# v1.net
KiCad netlist of a schematic drawn in EAGLE
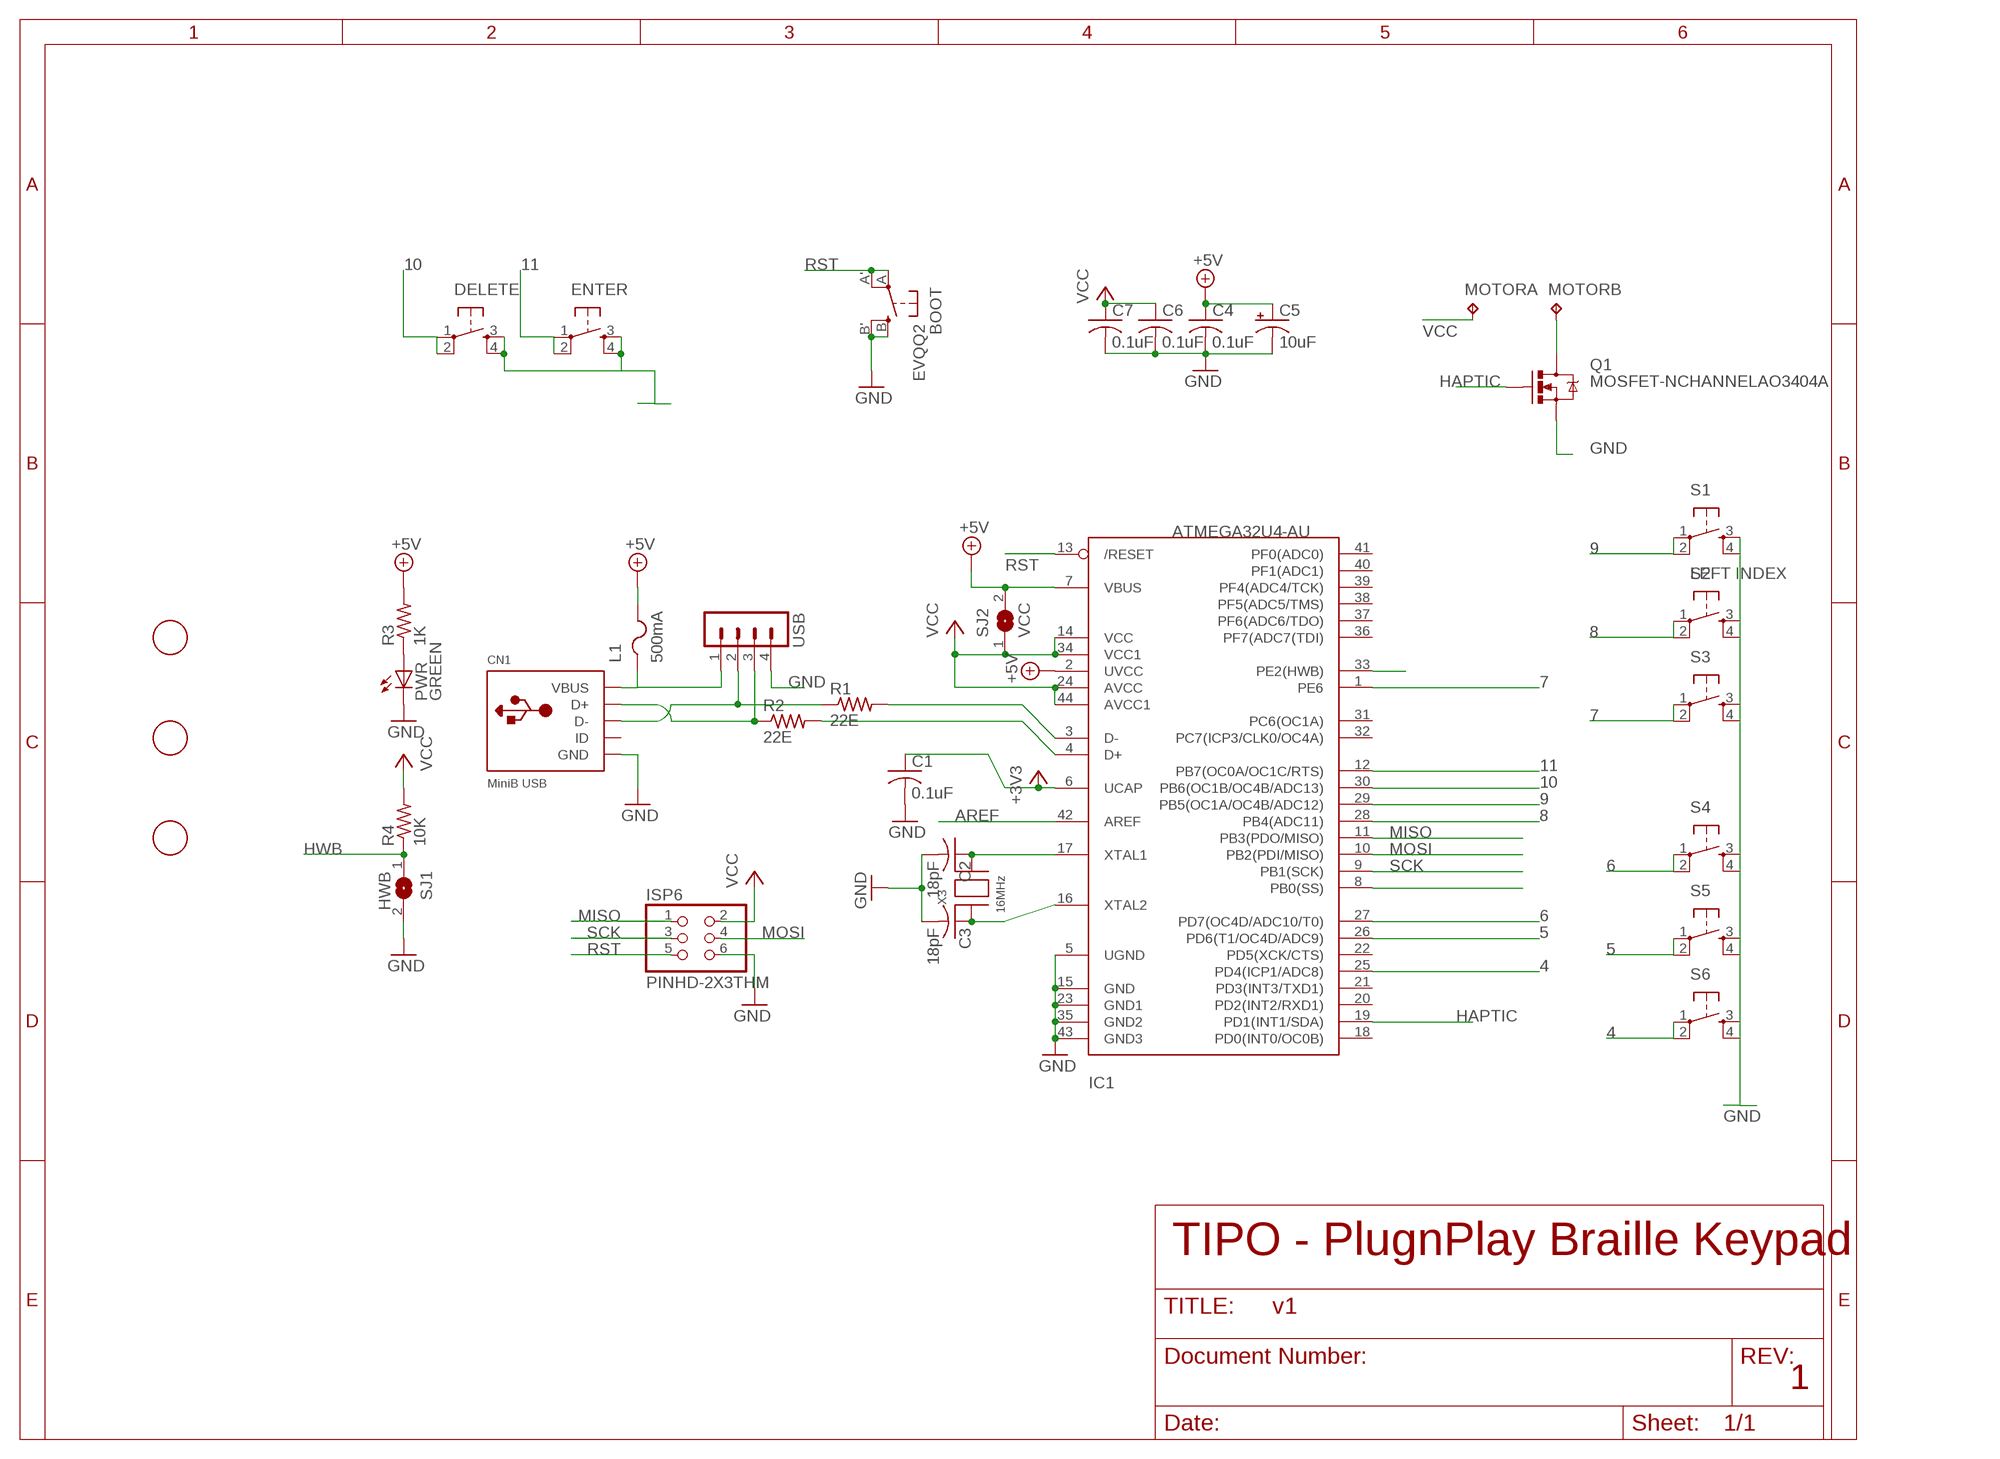
[diagram p0: schematic, sheet 1]

(export (version "E")
  (design (tool "Eeschema 10.0.6"))
  (components
    (comp (ref "BOOT")
      (value "EVQQ2")
      (footprint "eagle-import:EVQ-Q2")
      (libsource (lib "eagle-import") (part "EVQQ2"))
    )
    (comp (ref "C1")
      (value "0.1uF")
      (footprint "eagle-import:C0805K")
      (libsource (lib "eagle-import") (part "C-USC0805K"))
    )
    (comp (ref "C2")
      (value "18pF")
      (footprint "eagle-import:C0805K")
      (libsource (lib "eagle-import") (part "C-USC0805K"))
    )
    (comp (ref "C3")
      (value "18pF")
      (footprint "eagle-import:C0805K")
      (libsource (lib "eagle-import") (part "C-USC0805K"))
    )
    (comp (ref "C4")
      (value "0.1uF")
      (footprint "eagle-import:C0805K")
      (libsource (lib "eagle-import") (part "C-USC0805K"))
    )
    (comp (ref "C5")
      (value "10uF")
      (footprint "eagle-import:A_3216-18R")
      (libsource (lib "eagle-import") (part "CPOL-USA/3216-18R"))
    )
    (comp (ref "C6")
      (value "0.1uF")
      (footprint "eagle-import:C0805K")
      (libsource (lib "eagle-import") (part "C-USC0805K"))
    )
    (comp (ref "C7")
      (value "0.1uF")
      (footprint "eagle-import:C0805K")
      (libsource (lib "eagle-import") (part "C-USC0805K"))
    )
    (comp (ref "CN1")
      (value "MiniB USB")
      (footprint "eagle-import:USB-MINIB")
      (libsource (lib "eagle-import") (part "USBMINIB"))
    )
    (comp (ref "DELETE")
      (value "TAC_SWITCHPTH")
      (footprint "eagle-import:TACTILE-PTH")
      (libsource (lib "eagle-import") (part "TAC_SWITCHPTH"))
    )
    (comp (ref "ENTER")
      (value "TAC_SWITCHPTH")
      (footprint "eagle-import:TACTILE-PTH")
      (libsource (lib "eagle-import") (part "TAC_SWITCHPTH"))
    )
    (comp (ref "IC1")
      (value "ATMEGA32U4-AU")
      (footprint "eagle-import:TQFP44")
      (libsource (lib "eagle-import") (part "ATMEGA32U4-AU"))
    )
    (comp (ref "ISP6")
      (value "PINHD-2X3THM")
      (footprint "eagle-import:ISP6")
      (libsource (lib "eagle-import") (part "PINHD-2X3THM"))
    )
    (comp (ref "L1")
      (value "500mA")
      (footprint "eagle-import:R1206")
      (libsource (lib "eagle-import") (part "PTCFUSE-1206"))
    )
    (comp (ref "MOTOR")
      (value "TP2P2-38-17")
      (footprint "eagle-import:P2-38-17")
      (libsource (lib "eagle-import") (part "TP2P2-38-17"))
    )
    (comp (ref "PWR")
      (value "GREEN")
      (footprint "eagle-import:CHIPLED_0805")
      (libsource (lib "eagle-import") (part "LEDCHIPLED_0805"))
    )
    (comp (ref "Q1")
      (value "MOSFET-NCHANNELAO3404A")
      (footprint "eagle-import:SOT23-3")
      (libsource (lib "eagle-import") (part "MOSFET-NCHANNELAO3404A"))
    )
    (comp (ref "R1")
      (value "22E")
      (footprint "eagle-import:R0805")
      (libsource (lib "eagle-import") (part "R-US_R0805"))
    )
    (comp (ref "R2")
      (value "22E")
      (footprint "eagle-import:R0805")
      (libsource (lib "eagle-import") (part "R-US_R0805"))
    )
    (comp (ref "R3")
      (value "1K")
      (footprint "eagle-import:R0805")
      (libsource (lib "eagle-import") (part "R-US_R0805"))
    )
    (comp (ref "R4")
      (value "10K")
      (footprint "eagle-import:R0805")
      (libsource (lib "eagle-import") (part "R-US_R0805"))
    )
    (comp (ref "S1")
      (value "LEFT INDEX")
      (footprint "eagle-import:TACTILE-PTH")
      (libsource (lib "eagle-import") (part "TAC_SWITCHPTH"))
    )
    (comp (ref "S2")
      (value "TAC_SWITCHPTH")
      (footprint "eagle-import:TACTILE-PTH")
      (libsource (lib "eagle-import") (part "TAC_SWITCHPTH"))
    )
    (comp (ref "S3")
      (value "TAC_SWITCHPTH")
      (footprint "eagle-import:TACTILE-PTH")
      (libsource (lib "eagle-import") (part "TAC_SWITCHPTH"))
    )
    (comp (ref "S4")
      (value "TAC_SWITCHPTH")
      (footprint "eagle-import:TACTILE-PTH")
      (libsource (lib "eagle-import") (part "TAC_SWITCHPTH"))
    )
    (comp (ref "S5")
      (value "TAC_SWITCHPTH")
      (footprint "eagle-import:TACTILE-PTH")
      (libsource (lib "eagle-import") (part "TAC_SWITCHPTH"))
    )
    (comp (ref "S6")
      (value "TAC_SWITCHPTH")
      (footprint "eagle-import:TACTILE-PTH")
      (libsource (lib "eagle-import") (part "TAC_SWITCHPTH"))
    )
    (comp (ref "SJ1")
      (value "HWB")
      (footprint "eagle-import:SJ")
      (libsource (lib "eagle-import") (part "SJ"))
    )
    (comp (ref "SJ2")
      (value "VCC")
      (footprint "eagle-import:SJ")
      (libsource (lib "eagle-import") (part "SJ"))
    )
    (comp (ref "U$1")
      (value "FIDUCIAL")
      (footprint "eagle-import:FIDUCIAL_1MM")
      (libsource (lib "eagle-import") (part "FIDUCIAL"))
    )
    (comp (ref "U$2")
      (value "FIDUCIAL")
      (footprint "eagle-import:FIDUCIAL_1MM")
      (libsource (lib "eagle-import") (part "FIDUCIAL"))
    )
    (comp (ref "U$6")
      (value "FIDUCIAL")
      (footprint "eagle-import:FIDUCIAL_1MM")
      (libsource (lib "eagle-import") (part "FIDUCIAL"))
    )
    (comp (ref "USB")
      (value "MA04-1")
      (footprint "eagle-import:MA04-1")
      (libsource (lib "eagle-import") (part "MA04-1"))
    )
    (comp (ref "X3")
      (value "16MHz")
      (footprint "eagle-import:NX5032")
      (libsource (lib "eagle-import") (part "XTALNX5032"))
    )
  )
  (nets
    (net (code "1") (name "+3V3") (class "Default")
      (node (ref "C1") (pin "1") (pinfunction "1_1") (pintype "passive"))
      (node (ref "IC1") (pin "6") (pinfunction "UCAP_6") (pintype "bidirectional"))
    )
    (net (code "2") (name "+5V") (class "Default")
      (node (ref "C4") (pin "1") (pinfunction "1_1") (pintype "passive"))
      (node (ref "C5") (pin "+") (pinfunction "+_+") (pintype "passive"))
      (node (ref "IC1") (pin "2") (pinfunction "UVCC_2") (pintype "bidirectional"))
      (node (ref "IC1") (pin "7") (pinfunction "VBUS_7") (pintype "bidirectional"))
      (node (ref "L1") (pin "2") (pinfunction "2_2") (pintype "passive"))
      (node (ref "R3") (pin "2") (pinfunction "2_2") (pintype "passive"))
      (node (ref "SJ2") (pin "2") (pinfunction "2_2") (pintype "passive"))
    )
    (net (code "3") (name "/4") (class "Default")
      (node (ref "IC1") (pin "25") (pinfunction "PD4(ICP1/ADC8)_25") (pintype "bidirectional"))
      (node (ref "S6") (pin "1") (pinfunction "1_1") (pintype "passive"))
      (node (ref "S6") (pin "2") (pinfunction "2_2") (pintype "passive"))
    )
    (net (code "4") (name "/5") (class "Default")
      (node (ref "IC1") (pin "26") (pinfunction "PD6(T1/OC4D/ADC9)_26") (pintype "bidirectional"))
      (node (ref "S5") (pin "1") (pinfunction "1_1") (pintype "passive"))
      (node (ref "S5") (pin "2") (pinfunction "2_2") (pintype "passive"))
    )
    (net (code "5") (name "/6") (class "Default")
      (node (ref "IC1") (pin "27") (pinfunction "PD7(OC4D/ADC10/T0)_27") (pintype "bidirectional"))
      (node (ref "S4") (pin "1") (pinfunction "1_1") (pintype "passive"))
      (node (ref "S4") (pin "2") (pinfunction "2_2") (pintype "passive"))
    )
    (net (code "6") (name "/7") (class "Default")
      (node (ref "IC1") (pin "1") (pinfunction "PE6_1") (pintype "bidirectional"))
      (node (ref "S3") (pin "1") (pinfunction "1_1") (pintype "passive"))
      (node (ref "S3") (pin "2") (pinfunction "2_2") (pintype "passive"))
    )
    (net (code "7") (name "/8") (class "Default")
      (node (ref "IC1") (pin "28") (pinfunction "PB4(ADC11)_28") (pintype "bidirectional"))
      (node (ref "S2") (pin "1") (pinfunction "1_1") (pintype "passive"))
      (node (ref "S2") (pin "2") (pinfunction "2_2") (pintype "passive"))
    )
    (net (code "8") (name "/9") (class "Default")
      (node (ref "IC1") (pin "29") (pinfunction "PB5(OC1A/OC4B/ADC12)_29") (pintype "bidirectional"))
      (node (ref "S1") (pin "1") (pinfunction "1_1") (pintype "passive"))
      (node (ref "S1") (pin "2") (pinfunction "2_2") (pintype "passive"))
    )
    (net (code "9") (name "/10") (class "Default")
      (node (ref "DELETE") (pin "1") (pinfunction "1_1") (pintype "passive"))
      (node (ref "DELETE") (pin "2") (pinfunction "2_2") (pintype "passive"))
      (node (ref "IC1") (pin "30") (pinfunction "PB6(OC1B/OC4B/ADC13)_30") (pintype "bidirectional"))
    )
    (net (code "10") (name "/11") (class "Default")
      (node (ref "ENTER") (pin "1") (pinfunction "1_1") (pintype "passive"))
      (node (ref "ENTER") (pin "2") (pinfunction "2_2") (pintype "passive"))
      (node (ref "IC1") (pin "12") (pinfunction "PB7(OC0A/OC1C/RTS)_12") (pintype "bidirectional"))
    )
    (net (code "11") (name "/AREF") (class "Default")
      (node (ref "IC1") (pin "42") (pinfunction "AREF_42") (pintype "bidirectional"))
    )
    (net (code "12") (name "/HAPTIC") (class "Default")
      (node (ref "IC1") (pin "19") (pinfunction "PD1(INT1/SDA)_19") (pintype "bidirectional"))
      (node (ref "Q1") (pin "1") (pinfunction "G_1") (pintype "passive"))
    )
    (net (code "13") (name "/HWB") (class "Default")
      (node (ref "IC1") (pin "33") (pinfunction "PE2(HWB)_33") (pintype "bidirectional"))
      (node (ref "R4") (pin "1") (pinfunction "1_1") (pintype "passive"))
      (node (ref "SJ1") (pin "1") (pinfunction "1_1") (pintype "passive"))
    )
    (net (code "14") (name "/MISO") (class "Default")
      (node (ref "IC1") (pin "11") (pinfunction "PB3(PDO/MISO)_11") (pintype "bidirectional"))
      (node (ref "ISP6") (pin "1") (pinfunction "1_1") (pintype "passive"))
    )
    (net (code "15") (name "/MOSI") (class "Default")
      (node (ref "IC1") (pin "10") (pinfunction "PB2(PDI/MISO)_10") (pintype "bidirectional"))
      (node (ref "ISP6") (pin "4") (pinfunction "4_4") (pintype "passive"))
    )
    (net (code "16") (name "/RST") (class "Default")
      (node (ref "BOOT") (pin "A") (pinfunction "P_A") (pintype "passive"))
      (node (ref "BOOT") (pin "A'") (pinfunction "P1_A'") (pintype "passive"))
      (node (ref "IC1") (pin "13") (pinfunction "/RESET_13") (pintype "bidirectional"))
      (node (ref "ISP6") (pin "5") (pinfunction "5_5") (pintype "passive"))
    )
    (net (code "17") (name "/SCK") (class "Default")
      (node (ref "IC1") (pin "9") (pinfunction "PB1(SCK)_9") (pintype "bidirectional"))
      (node (ref "ISP6") (pin "3") (pinfunction "3_3") (pintype "passive"))
    )
    (net (code "18") (name "GND") (class "Default")
      (node (ref "BOOT") (pin "B") (pinfunction "S_B") (pintype "passive"))
      (node (ref "BOOT") (pin "B'") (pinfunction "S1_B'") (pintype "passive"))
      (node (ref "C1") (pin "2") (pinfunction "2_2") (pintype "passive"))
      (node (ref "C2") (pin "2") (pinfunction "2_2") (pintype "passive"))
      (node (ref "C3") (pin "2") (pinfunction "2_2") (pintype "passive"))
      (node (ref "C4") (pin "2") (pinfunction "2_2") (pintype "passive"))
      (node (ref "C5") (pin "-") (pinfunction "-_-") (pintype "passive"))
      (node (ref "C6") (pin "2") (pinfunction "2_2") (pintype "passive"))
      (node (ref "C7") (pin "2") (pinfunction "2_2") (pintype "passive"))
      (node (ref "CN1") (pin "GND") (pinfunction "GND_GND") (pintype "power_in"))
      (node (ref "DELETE") (pin "3") (pinfunction "3_3") (pintype "passive"))
      (node (ref "DELETE") (pin "4") (pinfunction "4_4") (pintype "passive"))
      (node (ref "ENTER") (pin "3") (pinfunction "3_3") (pintype "passive"))
      (node (ref "ENTER") (pin "4") (pinfunction "4_4") (pintype "passive"))
      (node (ref "IC1") (pin "15") (pinfunction "GND_15") (pintype "bidirectional"))
      (node (ref "IC1") (pin "23") (pinfunction "GND1_23") (pintype "bidirectional"))
      (node (ref "IC1") (pin "35") (pinfunction "GND2_35") (pintype "bidirectional"))
      (node (ref "IC1") (pin "43") (pinfunction "GND3_43") (pintype "bidirectional"))
      (node (ref "IC1") (pin "5") (pinfunction "UGND_5") (pintype "bidirectional"))
      (node (ref "ISP6") (pin "6") (pinfunction "6_6") (pintype "passive"))
      (node (ref "PWR") (pin "C") (pinfunction "C_C") (pintype "passive"))
      (node (ref "Q1") (pin "2") (pinfunction "S_2") (pintype "passive"))
      (node (ref "S1") (pin "3") (pinfunction "3_3") (pintype "passive"))
      (node (ref "S1") (pin "4") (pinfunction "4_4") (pintype "passive"))
      (node (ref "S2") (pin "3") (pinfunction "3_3") (pintype "passive"))
      (node (ref "S2") (pin "4") (pinfunction "4_4") (pintype "passive"))
      (node (ref "S3") (pin "3") (pinfunction "3_3") (pintype "passive"))
      (node (ref "S3") (pin "4") (pinfunction "4_4") (pintype "passive"))
      (node (ref "S4") (pin "3") (pinfunction "3_3") (pintype "passive"))
      (node (ref "S4") (pin "4") (pinfunction "4_4") (pintype "passive"))
      (node (ref "S5") (pin "3") (pinfunction "3_3") (pintype "passive"))
      (node (ref "S5") (pin "4") (pinfunction "4_4") (pintype "passive"))
      (node (ref "S6") (pin "3") (pinfunction "3_3") (pintype "passive"))
      (node (ref "S6") (pin "4") (pinfunction "4_4") (pintype "passive"))
      (node (ref "SJ1") (pin "2") (pinfunction "2_2") (pintype "passive"))
      (node (ref "USB") (pin "4") (pinfunction "4_4") (pintype "passive"))
    )
    (net (code "19") (name "Net-(CN1-PadD+)") (class "Default")
      (node (ref "CN1") (pin "D+") (pinfunction "D+_D+") (pintype "bidirectional"))
      (node (ref "R2") (pin "1") (pinfunction "1_1") (pintype "passive"))
      (node (ref "USB") (pin "3") (pinfunction "3_3") (pintype "passive"))
    )
    (net (code "20") (name "Net-(CN1-PadD-)") (class "Default")
      (node (ref "CN1") (pin "D-") (pinfunction "D-_D-") (pintype "bidirectional"))
      (node (ref "R1") (pin "1") (pinfunction "1_1") (pintype "passive"))
      (node (ref "USB") (pin "2") (pinfunction "2_2") (pintype "passive"))
    )
    (net (code "21") (name "Net-(CN1-PadVBUS)") (class "Default")
      (node (ref "CN1") (pin "VBUS") (pinfunction "VBUS_VBUS") (pintype "power_in"))
      (node (ref "L1") (pin "1") (pinfunction "1_1") (pintype "passive"))
      (node (ref "USB") (pin "1") (pinfunction "1_1") (pintype "passive"))
    )
    (net (code "22") (name "Net-(IC1-D+)") (class "Default")
      (node (ref "IC1") (pin "4") (pinfunction "D+_4") (pintype "bidirectional"))
      (node (ref "R2") (pin "2") (pinfunction "2_2") (pintype "passive"))
    )
    (net (code "23") (name "Net-(IC1-D-)") (class "Default")
      (node (ref "IC1") (pin "3") (pinfunction "D-_3") (pintype "bidirectional"))
      (node (ref "R1") (pin "2") (pinfunction "2_2") (pintype "passive"))
    )
    (net (code "24") (name "Net-(IC1-XTAL1)") (class "Default")
      (node (ref "C2") (pin "1") (pinfunction "1_1") (pintype "passive"))
      (node (ref "IC1") (pin "17") (pinfunction "XTAL1_17") (pintype "bidirectional"))
      (node (ref "X3") (pin "P$2") (pinfunction "P$2_P$2") (pintype "bidirectional"))
    )
    (net (code "25") (name "Net-(IC1-XTAL2)") (class "Default")
      (node (ref "C3") (pin "1") (pinfunction "1_1") (pintype "passive"))
      (node (ref "IC1") (pin "16") (pinfunction "XTAL2_16") (pintype "bidirectional"))
      (node (ref "X3") (pin "P$1") (pinfunction "P$1_P$1") (pintype "bidirectional"))
    )
    (net (code "26") (name "Net-(MOTORB-TP)") (class "Default")
      (node (ref "MOTOR") (pin "TP-2") (pinfunction "TP_TP-2") (pintype "input"))
      (node (ref "Q1") (pin "3") (pinfunction "D_3") (pintype "passive"))
    )
    (net (code "27") (name "Net-(PWR-PadA)") (class "Default")
      (node (ref "PWR") (pin "A") (pinfunction "A_A") (pintype "passive"))
      (node (ref "R3") (pin "1") (pinfunction "1_1") (pintype "passive"))
    )
    (net (code "28") (name "VCC") (class "Default")
      (node (ref "C6") (pin "1") (pinfunction "1_1") (pintype "passive"))
      (node (ref "C7") (pin "1") (pinfunction "1_1") (pintype "passive"))
      (node (ref "IC1") (pin "14") (pinfunction "VCC_14") (pintype "bidirectional"))
      (node (ref "IC1") (pin "24") (pinfunction "AVCC_24") (pintype "bidirectional"))
      (node (ref "IC1") (pin "34") (pinfunction "VCC1_34") (pintype "bidirectional"))
      (node (ref "IC1") (pin "44") (pinfunction "AVCC1_44") (pintype "bidirectional"))
      (node (ref "ISP6") (pin "2") (pinfunction "2_2") (pintype "passive"))
      (node (ref "MOTOR") (pin "TP-1") (pinfunction "TP_TP-1") (pintype "input"))
      (node (ref "R4") (pin "2") (pinfunction "2_2") (pintype "passive"))
      (node (ref "SJ2") (pin "1") (pinfunction "1_1") (pintype "passive"))
    )
    (net (code "29") (name "unconnected-(CN1-PadID)") (class "Default")
      (node (ref "CN1") (pin "ID") (pinfunction "ID_ID") (pintype "bidirectional"))
    )
    (net (code "30") (name "unconnected-(IC1-PB0(SS)-Pad8)") (class "Default")
      (node (ref "IC1") (pin "8") (pinfunction "PB0(SS)_8") (pintype "bidirectional"))
    )
    (net (code "31") (name "unconnected-(IC1-PC6(OC1A)-Pad31)") (class "Default")
      (node (ref "IC1") (pin "31") (pinfunction "PC6(OC1A)_31") (pintype "bidirectional"))
    )
    (net (code "32") (name "unconnected-(IC1-PC7(ICP3{slash}CLK0{slash}OC4A)-Pad32)") (class "Default")
      (node (ref "IC1") (pin "32") (pinfunction "PC7(ICP3/CLK0/OC4A)_32") (pintype "bidirectional"))
    )
    (net (code "33") (name "unconnected-(IC1-PD0(INT0{slash}OC0B)-Pad18)") (class "Default")
      (node (ref "IC1") (pin "18") (pinfunction "PD0(INT0/OC0B)_18") (pintype "bidirectional"))
    )
    (net (code "34") (name "unconnected-(IC1-PD2(INT2{slash}RXD1)-Pad20)") (class "Default")
      (node (ref "IC1") (pin "20") (pinfunction "PD2(INT2/RXD1)_20") (pintype "bidirectional"))
    )
    (net (code "35") (name "unconnected-(IC1-PD3(INT3{slash}TXD1)-Pad21)") (class "Default")
      (node (ref "IC1") (pin "21") (pinfunction "PD3(INT3/TXD1)_21") (pintype "bidirectional"))
    )
    (net (code "36") (name "unconnected-(IC1-PD5(XCK{slash}CTS)-Pad22)") (class "Default")
      (node (ref "IC1") (pin "22") (pinfunction "PD5(XCK/CTS)_22") (pintype "bidirectional"))
    )
    (net (code "37") (name "unconnected-(IC1-PF0(ADC0)-Pad41)") (class "Default")
      (node (ref "IC1") (pin "41") (pinfunction "PF0(ADC0)_41") (pintype "bidirectional"))
    )
    (net (code "38") (name "unconnected-(IC1-PF1(ADC1)-Pad40)") (class "Default")
      (node (ref "IC1") (pin "40") (pinfunction "PF1(ADC1)_40") (pintype "bidirectional"))
    )
    (net (code "39") (name "unconnected-(IC1-PF4(ADC4{slash}TCK)-Pad39)") (class "Default")
      (node (ref "IC1") (pin "39") (pinfunction "PF4(ADC4/TCK)_39") (pintype "bidirectional"))
    )
    (net (code "40") (name "unconnected-(IC1-PF5(ADC5{slash}TMS)-Pad38)") (class "Default")
      (node (ref "IC1") (pin "38") (pinfunction "PF5(ADC5/TMS)_38") (pintype "bidirectional"))
    )
    (net (code "41") (name "unconnected-(IC1-PF6(ADC6{slash}TDO)-Pad37)") (class "Default")
      (node (ref "IC1") (pin "37") (pinfunction "PF6(ADC6/TDO)_37") (pintype "bidirectional"))
    )
    (net (code "42") (name "unconnected-(IC1-PF7(ADC7(TDI)-Pad36)") (class "Default")
      (node (ref "IC1") (pin "36") (pinfunction "PF7(ADC7(TDI)_36") (pintype "bidirectional"))
    )
  )
)
